# ds7_redraw.net
KiCad netlist of a schematic drawn in EAGLE
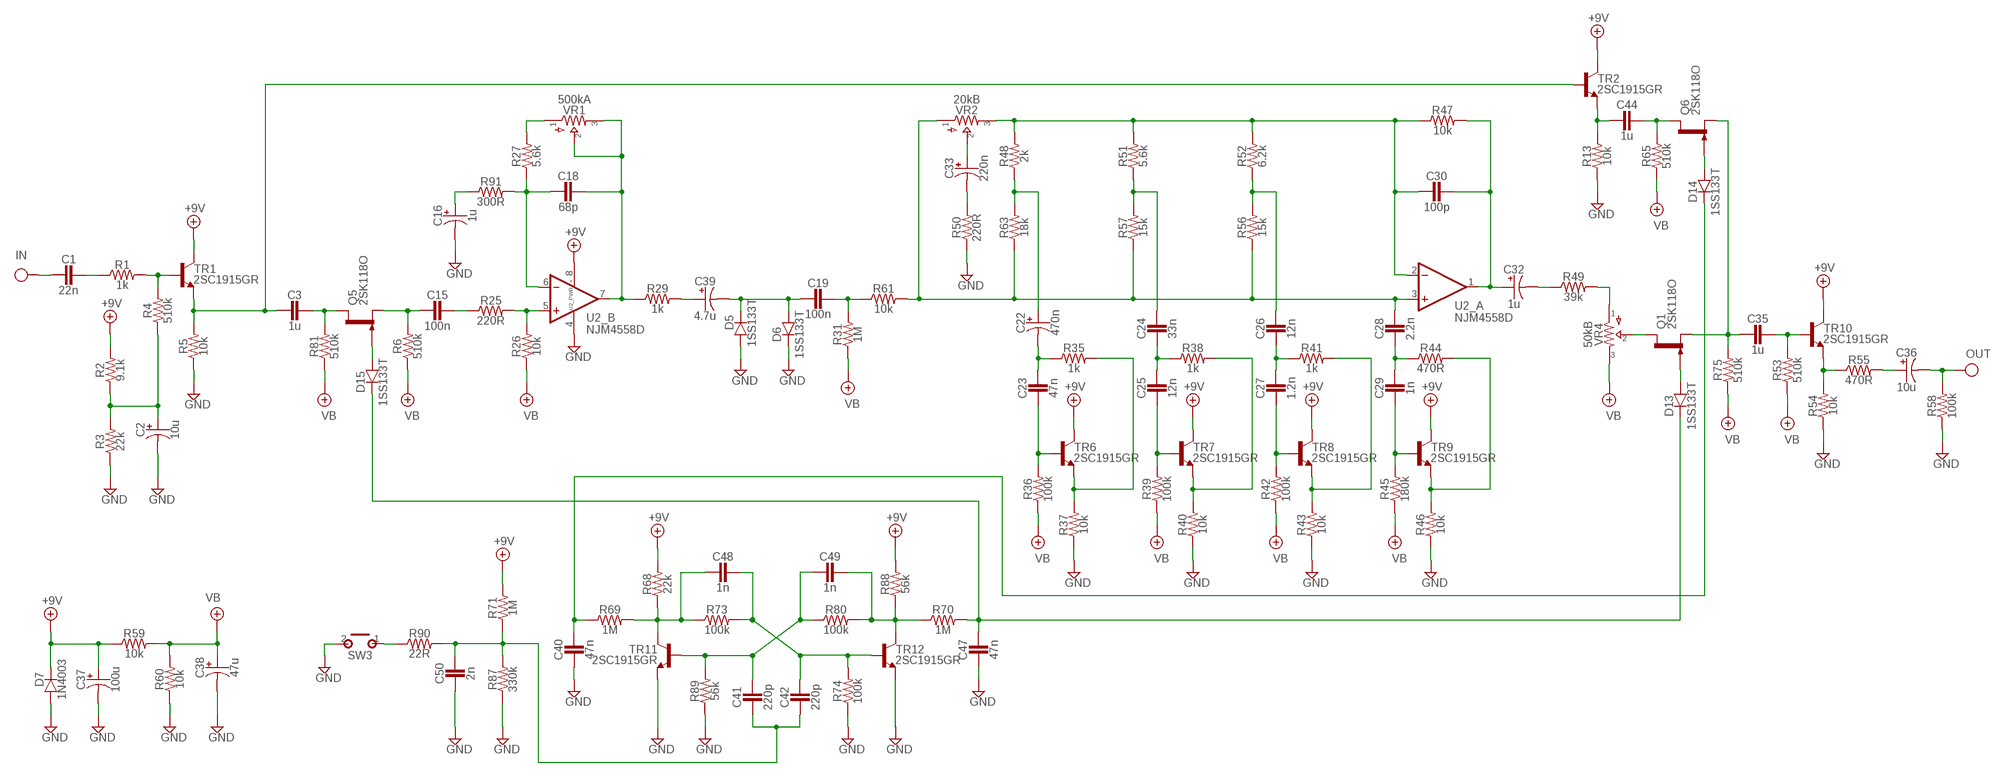
[diagram p0: schematic, sheet 1]

(export (version "E")
  (design (tool "Eeschema 10.0.6"))
  (components
    (comp (ref "C1")
      (value "22n")
      (footprint "eagle-import:BOX_SMALL")
      (libsource (lib "eagle-import") (part "CER/FILMBOX.1"))
    )
    (comp (ref "C2")
      (value "10u")
      (footprint "eagle-import:040_020")
      (libsource (lib "eagle-import") (part "0400"))
    )
    (comp (ref "C3")
      (value "1u")
      (footprint "eagle-import:BOX_SMALL")
      (libsource (lib "eagle-import") (part "CER/FILMBOX.1"))
    )
    (comp (ref "C15")
      (value "100n")
      (footprint "eagle-import:BOX_SMALL")
      (libsource (lib "eagle-import") (part "CER/FILMBOX.1"))
    )
    (comp (ref "C16")
      (value "1u")
      (footprint "eagle-import:040_020")
      (libsource (lib "eagle-import") (part "0400"))
    )
    (comp (ref "C18")
      (value "68p")
      (footprint "eagle-import:BOX_SMALL")
      (libsource (lib "eagle-import") (part "CER/FILMBOX.1"))
    )
    (comp (ref "C19")
      (value "100n")
      (footprint "eagle-import:BOX_SMALL")
      (libsource (lib "eagle-import") (part "CER/FILMBOX.1"))
    )
    (comp (ref "C22")
      (value "470n")
      (footprint "eagle-import:040_020")
      (libsource (lib "eagle-import") (part "0400"))
    )
    (comp (ref "C23")
      (value "47n")
      (footprint "eagle-import:BOX_SMALL")
      (libsource (lib "eagle-import") (part "CER/FILMBOX.1"))
    )
    (comp (ref "C24")
      (value "33n")
      (footprint "eagle-import:BOX_SMALL")
      (libsource (lib "eagle-import") (part "CER/FILMBOX.1"))
    )
    (comp (ref "C25")
      (value "12n")
      (footprint "eagle-import:BOX_SMALL")
      (libsource (lib "eagle-import") (part "CER/FILMBOX.1"))
    )
    (comp (ref "C26")
      (value "12n")
      (footprint "eagle-import:BOX_SMALL")
      (libsource (lib "eagle-import") (part "CER/FILMBOX.1"))
    )
    (comp (ref "C27")
      (value "1.2n")
      (footprint "eagle-import:BOX_SMALL")
      (libsource (lib "eagle-import") (part "CER/FILMBOX.1"))
    )
    (comp (ref "C28")
      (value "2.2n")
      (footprint "eagle-import:BOX_SMALL")
      (libsource (lib "eagle-import") (part "CER/FILMBOX.1"))
    )
    (comp (ref "C29")
      (value "1n")
      (footprint "eagle-import:BOX_SMALL")
      (libsource (lib "eagle-import") (part "CER/FILMBOX.1"))
    )
    (comp (ref "C30")
      (value "100p")
      (footprint "eagle-import:BOX_SMALL")
      (libsource (lib "eagle-import") (part "CER/FILMBOX.1"))
    )
    (comp (ref "C32")
      (value "1u")
      (footprint "eagle-import:040_020")
      (libsource (lib "eagle-import") (part "0400"))
    )
    (comp (ref "C33")
      (value "220n")
      (footprint "eagle-import:040_020")
      (libsource (lib "eagle-import") (part "0400"))
    )
    (comp (ref "C35")
      (value "1u")
      (footprint "eagle-import:BOX_SMALL")
      (libsource (lib "eagle-import") (part "CER/FILMBOX.1"))
    )
    (comp (ref "C36")
      (value "10u")
      (footprint "eagle-import:040_020")
      (libsource (lib "eagle-import") (part "0400"))
    )
    (comp (ref "C37")
      (value "100u")
      (footprint "eagle-import:040_020")
      (libsource (lib "eagle-import") (part "0400"))
    )
    (comp (ref "C38")
      (value "47u")
      (footprint "eagle-import:040_020")
      (libsource (lib "eagle-import") (part "0400"))
    )
    (comp (ref "C39")
      (value "4.7u")
      (footprint "eagle-import:040_020")
      (libsource (lib "eagle-import") (part "0400"))
    )
    (comp (ref "C40")
      (value "47n")
      (footprint "eagle-import:BOX_SMALL")
      (libsource (lib "eagle-import") (part "CER/FILMBOX.1"))
    )
    (comp (ref "C41")
      (value "220p")
      (footprint "eagle-import:BOX_SMALL")
      (libsource (lib "eagle-import") (part "CER/FILMBOX.1"))
    )
    (comp (ref "C42")
      (value "220p")
      (footprint "eagle-import:BOX_SMALL")
      (libsource (lib "eagle-import") (part "CER/FILMBOX.1"))
    )
    (comp (ref "C44")
      (value "1u")
      (footprint "eagle-import:BOX_SMALL")
      (libsource (lib "eagle-import") (part "CER/FILMBOX.1"))
    )
    (comp (ref "C47")
      (value "47n")
      (footprint "eagle-import:BOX_SMALL")
      (libsource (lib "eagle-import") (part "CER/FILMBOX.1"))
    )
    (comp (ref "C48")
      (value "1n")
      (footprint "eagle-import:BOX_SMALL")
      (libsource (lib "eagle-import") (part "CER/FILMBOX.1"))
    )
    (comp (ref "C49")
      (value "1n")
      (footprint "eagle-import:BOX_SMALL")
      (libsource (lib "eagle-import") (part "CER/FILMBOX.1"))
    )
    (comp (ref "C50")
      (value "2n")
      (footprint "eagle-import:BOX_SMALL")
      (libsource (lib "eagle-import") (part "CER/FILMBOX.1"))
    )
    (comp (ref "D5")
      (value "1SS133T")
      (footprint "eagle-import:DO41-2")
      (libsource (lib "eagle-import") (part "DO41.2"))
    )
    (comp (ref "D6")
      (value "1SS133T")
      (footprint "eagle-import:DO41-2")
      (libsource (lib "eagle-import") (part "DO41.2"))
    )
    (comp (ref "D7")
      (value "1N4003")
      (footprint "eagle-import:DO41-2")
      (libsource (lib "eagle-import") (part "DO41.2"))
    )
    (comp (ref "D13")
      (value "1SS133T")
      (footprint "eagle-import:DO41-2")
      (libsource (lib "eagle-import") (part "DO41.2"))
    )
    (comp (ref "D14")
      (value "1SS133T")
      (footprint "eagle-import:DO41-2")
      (libsource (lib "eagle-import") (part "DO41.2"))
    )
    (comp (ref "D15")
      (value "1SS133T")
      (footprint "eagle-import:DO41-2")
      (libsource (lib "eagle-import") (part "DO41.2"))
    )
    (comp (ref "Q1")
      (value "2SK118O")
      (footprint "eagle-import:TO92-")
      (libsource (lib "eagle-import") (part "2N5457"))
    )
    (comp (ref "Q5")
      (value "2SK118O")
      (footprint "eagle-import:TO92-")
      (libsource (lib "eagle-import") (part "2N5457"))
    )
    (comp (ref "Q6")
      (value "2SK118O")
      (footprint "eagle-import:TO92-")
      (libsource (lib "eagle-import") (part "2N5457"))
    )
    (comp (ref "R1")
      (value "1k")
      (footprint "eagle-import:R0207_3")
      (libsource (lib "eagle-import") (part "R_.3B"))
    )
    (comp (ref "R2")
      (value "9.1k")
      (footprint "eagle-import:R0207_3")
      (libsource (lib "eagle-import") (part "R_.3B"))
    )
    (comp (ref "R3")
      (value "22k")
      (footprint "eagle-import:R0207_3")
      (libsource (lib "eagle-import") (part "R_.3B"))
    )
    (comp (ref "R4")
      (value "510k")
      (footprint "eagle-import:R0207_3")
      (libsource (lib "eagle-import") (part "R_.3B"))
    )
    (comp (ref "R5")
      (value "10k")
      (footprint "eagle-import:R0207_3")
      (libsource (lib "eagle-import") (part "R_.3B"))
    )
    (comp (ref "R6")
      (value "510k")
      (footprint "eagle-import:R0207_3")
      (libsource (lib "eagle-import") (part "R_.3B"))
    )
    (comp (ref "R13")
      (value "10k")
      (footprint "eagle-import:R0207_3")
      (libsource (lib "eagle-import") (part "R_.3B"))
    )
    (comp (ref "R25")
      (value "220R")
      (footprint "eagle-import:R0207_3")
      (libsource (lib "eagle-import") (part "R_.3B"))
    )
    (comp (ref "R26")
      (value "10k")
      (footprint "eagle-import:R0207_3")
      (libsource (lib "eagle-import") (part "R_.3B"))
    )
    (comp (ref "R27")
      (value "5.6k")
      (footprint "eagle-import:R0207_3")
      (libsource (lib "eagle-import") (part "R_.3B"))
    )
    (comp (ref "R29")
      (value "1k")
      (footprint "eagle-import:R0207_3")
      (libsource (lib "eagle-import") (part "R_.3B"))
    )
    (comp (ref "R31")
      (value "1M")
      (footprint "eagle-import:R0207_3")
      (libsource (lib "eagle-import") (part "R_.3B"))
    )
    (comp (ref "R35")
      (value "1k")
      (footprint "eagle-import:R0207_3")
      (libsource (lib "eagle-import") (part "R_.3B"))
    )
    (comp (ref "R36")
      (value "100k")
      (footprint "eagle-import:R0207_3")
      (libsource (lib "eagle-import") (part "R_.3B"))
    )
    (comp (ref "R37")
      (value "10k")
      (footprint "eagle-import:R0207_3")
      (libsource (lib "eagle-import") (part "R_.3B"))
    )
    (comp (ref "R38")
      (value "1k")
      (footprint "eagle-import:R0207_3")
      (libsource (lib "eagle-import") (part "R_.3B"))
    )
    (comp (ref "R39")
      (value "100k")
      (footprint "eagle-import:R0207_3")
      (libsource (lib "eagle-import") (part "R_.3B"))
    )
    (comp (ref "R40")
      (value "10k")
      (footprint "eagle-import:R0207_3")
      (libsource (lib "eagle-import") (part "R_.3B"))
    )
    (comp (ref "R41")
      (value "1k")
      (footprint "eagle-import:R0207_3")
      (libsource (lib "eagle-import") (part "R_.3B"))
    )
    (comp (ref "R42")
      (value "100k")
      (footprint "eagle-import:R0207_3")
      (libsource (lib "eagle-import") (part "R_.3B"))
    )
    (comp (ref "R43")
      (value "10k")
      (footprint "eagle-import:R0207_3")
      (libsource (lib "eagle-import") (part "R_.3B"))
    )
    (comp (ref "R44")
      (value "470R")
      (footprint "eagle-import:R0207_3")
      (libsource (lib "eagle-import") (part "R_.3B"))
    )
    (comp (ref "R45")
      (value "180k")
      (footprint "eagle-import:R0207_3")
      (libsource (lib "eagle-import") (part "R_.3B"))
    )
    (comp (ref "R46")
      (value "10k")
      (footprint "eagle-import:R0207_3")
      (libsource (lib "eagle-import") (part "R_.3B"))
    )
    (comp (ref "R47")
      (value "10k")
      (footprint "eagle-import:R0207_3")
      (libsource (lib "eagle-import") (part "R_.3B"))
    )
    (comp (ref "R48")
      (value "2k")
      (footprint "eagle-import:R0207_3")
      (libsource (lib "eagle-import") (part "R_.3B"))
    )
    (comp (ref "R49")
      (value "39k")
      (footprint "eagle-import:R0207_3")
      (libsource (lib "eagle-import") (part "R_.3B"))
    )
    (comp (ref "R50")
      (value "220R")
      (footprint "eagle-import:R0207_3")
      (libsource (lib "eagle-import") (part "R_.3B"))
    )
    (comp (ref "R51")
      (value "5.6k")
      (footprint "eagle-import:R0207_3")
      (libsource (lib "eagle-import") (part "R_.3B"))
    )
    (comp (ref "R52")
      (value "6.2k")
      (footprint "eagle-import:R0207_3")
      (libsource (lib "eagle-import") (part "R_.3B"))
    )
    (comp (ref "R53")
      (value "510k")
      (footprint "eagle-import:R0207_3")
      (libsource (lib "eagle-import") (part "R_.3B"))
    )
    (comp (ref "R54")
      (value "10k")
      (footprint "eagle-import:R0207_3")
      (libsource (lib "eagle-import") (part "R_.3B"))
    )
    (comp (ref "R55")
      (value "470R")
      (footprint "eagle-import:R0207_3")
      (libsource (lib "eagle-import") (part "R_.3B"))
    )
    (comp (ref "R56")
      (value "15k")
      (footprint "eagle-import:R0207_3")
      (libsource (lib "eagle-import") (part "R_.3B"))
    )
    (comp (ref "R57")
      (value "15k")
      (footprint "eagle-import:R0207_3")
      (libsource (lib "eagle-import") (part "R_.3B"))
    )
    (comp (ref "R58")
      (value "100k")
      (footprint "eagle-import:R0207_3")
      (libsource (lib "eagle-import") (part "R_.3B"))
    )
    (comp (ref "R59")
      (value "10k")
      (footprint "eagle-import:R0207_3")
      (libsource (lib "eagle-import") (part "R_.3B"))
    )
    (comp (ref "R60")
      (value "10k")
      (footprint "eagle-import:R0207_3")
      (libsource (lib "eagle-import") (part "R_.3B"))
    )
    (comp (ref "R61")
      (value "10k")
      (footprint "eagle-import:R0207_3")
      (libsource (lib "eagle-import") (part "R_.3B"))
    )
    (comp (ref "R63")
      (value "18k")
      (footprint "eagle-import:R0207_3")
      (libsource (lib "eagle-import") (part "R_.3B"))
    )
    (comp (ref "R65")
      (value "510k")
      (footprint "eagle-import:R0207_3")
      (libsource (lib "eagle-import") (part "R_.3B"))
    )
    (comp (ref "R68")
      (value "22k")
      (footprint "eagle-import:R0207_3")
      (libsource (lib "eagle-import") (part "R_.3B"))
    )
    (comp (ref "R69")
      (value "1M")
      (footprint "eagle-import:R0207_3")
      (libsource (lib "eagle-import") (part "R_.3B"))
    )
    (comp (ref "R70")
      (value "1M")
      (footprint "eagle-import:R0207_3")
      (libsource (lib "eagle-import") (part "R_.3B"))
    )
    (comp (ref "R71")
      (value "1M")
      (footprint "eagle-import:R0207_3")
      (libsource (lib "eagle-import") (part "R_.3B"))
    )
    (comp (ref "R73")
      (value "100k")
      (footprint "eagle-import:R0207_3")
      (libsource (lib "eagle-import") (part "R_.3B"))
    )
    (comp (ref "R74")
      (value "100k")
      (footprint "eagle-import:R0207_3")
      (libsource (lib "eagle-import") (part "R_.3B"))
    )
    (comp (ref "R75")
      (value "510k")
      (footprint "eagle-import:R0207_3")
      (libsource (lib "eagle-import") (part "R_.3B"))
    )
    (comp (ref "R80")
      (value "100k")
      (footprint "eagle-import:R0207_3")
      (libsource (lib "eagle-import") (part "R_.3B"))
    )
    (comp (ref "R81")
      (value "510k")
      (footprint "eagle-import:R0207_3")
      (libsource (lib "eagle-import") (part "R_.3B"))
    )
    (comp (ref "R87")
      (value "330k")
      (footprint "eagle-import:R0207_3")
      (libsource (lib "eagle-import") (part "R_.3B"))
    )
    (comp (ref "R88")
      (value "56k")
      (footprint "eagle-import:R0207_3")
      (libsource (lib "eagle-import") (part "R_.3B"))
    )
    (comp (ref "R89")
      (value "56k")
      (footprint "eagle-import:R0207_3")
      (libsource (lib "eagle-import") (part "R_.3B"))
    )
    (comp (ref "R90")
      (value "22R")
      (footprint "eagle-import:R0207_3")
      (libsource (lib "eagle-import") (part "R_.3B"))
    )
    (comp (ref "R91")
      (value "300R")
      (footprint "eagle-import:R0207_3")
      (libsource (lib "eagle-import") (part "R_.3B"))
    )
    (comp (ref "SW3")
      (value "MOMENTARY")
      (footprint "eagle-import:SPST")
      (libsource (lib "eagle-import") (part "MOMENTARY"))
    )
    (comp (ref "TR1")
      (value "2SC1915GR")
      (footprint "eagle-import:TO92-")
      (libsource (lib "eagle-import") (part "2SC828A"))
    )
    (comp (ref "TR2")
      (value "2SC1915GR")
      (footprint "eagle-import:TO92-")
      (libsource (lib "eagle-import") (part "2SC828A"))
    )
    (comp (ref "TR6")
      (value "2SC1915GR")
      (footprint "eagle-import:TO92-")
      (libsource (lib "eagle-import") (part "2SC828A"))
    )
    (comp (ref "TR7")
      (value "2SC1915GR")
      (footprint "eagle-import:TO92-")
      (libsource (lib "eagle-import") (part "2SC828A"))
    )
    (comp (ref "TR8")
      (value "2SC1915GR")
      (footprint "eagle-import:TO92-")
      (libsource (lib "eagle-import") (part "2SC828A"))
    )
    (comp (ref "TR9")
      (value "2SC1915GR")
      (footprint "eagle-import:TO92-")
      (libsource (lib "eagle-import") (part "2SC828A"))
    )
    (comp (ref "TR10")
      (value "2SC1915GR")
      (footprint "eagle-import:TO92-")
      (libsource (lib "eagle-import") (part "2SC828A"))
    )
    (comp (ref "TR11")
      (value "2SC1915GR")
      (footprint "eagle-import:TO92-")
      (libsource (lib "eagle-import") (part "2SC828A"))
    )
    (comp (ref "TR12")
      (value "2SC1915GR")
      (footprint "eagle-import:TO92-")
      (libsource (lib "eagle-import") (part "2SC828A"))
    )
    (comp (ref "U2")
      (value "NJM4558D")
      (footprint "eagle-import:DIL0")
      (libsource (lib "eagle-import") (part "DUALTH"))
    )
    (comp (ref "VR1")
      (value "500kA")
      (footprint "eagle-import:16MM")
      (libsource (lib "eagle-import") (part "POTS16MM"))
    )
    (comp (ref "VR2")
      (value "20kB")
      (footprint "eagle-import:16MM")
      (libsource (lib "eagle-import") (part "POTS16MM"))
    )
    (comp (ref "VR4")
      (value "50kB")
      (footprint "eagle-import:16MM")
      (libsource (lib "eagle-import") (part "POTS16MM"))
    )
  )
  (nets
    (net (code "1") (name "+9V") (class "Default")
      (node (ref "C37") (pin "+") (pinfunction "+_+") (pintype "passive"))
      (node (ref "D7") (pin "C") (pinfunction "C_C") (pintype "passive"))
      (node (ref "R2") (pin "2") (pinfunction "2_2") (pintype "passive"))
      (node (ref "R59") (pin "1") (pinfunction "1_1") (pintype "passive"))
      (node (ref "R68") (pin "2") (pinfunction "2_2") (pintype "passive"))
      (node (ref "R71") (pin "2") (pinfunction "2_2") (pintype "passive"))
      (node (ref "R88") (pin "2") (pinfunction "2_2") (pintype "passive"))
      (node (ref "TR1") (pin "2") (pinfunction "C_2") (pintype "passive"))
      (node (ref "TR10") (pin "2") (pinfunction "C_2") (pintype "passive"))
      (node (ref "TR2") (pin "2") (pinfunction "C_2") (pintype "passive"))
      (node (ref "TR6") (pin "2") (pinfunction "C_2") (pintype "passive"))
      (node (ref "TR7") (pin "2") (pinfunction "C_2") (pintype "passive"))
      (node (ref "TR8") (pin "2") (pinfunction "C_2") (pintype "passive"))
      (node (ref "TR9") (pin "2") (pinfunction "C_2") (pintype "passive"))
      (node (ref "U2") (pin "8") (pinfunction "V+_8") (pintype "power_in"))
    )
    (net (code "2") (name "GND") (class "Default")
      (node (ref "C16") (pin "-") (pinfunction "-_-") (pintype "passive"))
      (node (ref "C2") (pin "-") (pinfunction "-_-") (pintype "passive"))
      (node (ref "C37") (pin "-") (pinfunction "-_-") (pintype "passive"))
      (node (ref "C38") (pin "-") (pinfunction "-_-") (pintype "passive"))
      (node (ref "C40") (pin "2") (pinfunction "2_2") (pintype "passive"))
      (node (ref "C47") (pin "2") (pinfunction "2_2") (pintype "passive"))
      (node (ref "C50") (pin "2") (pinfunction "2_2") (pintype "passive"))
      (node (ref "D5") (pin "A") (pinfunction "A_A") (pintype "passive"))
      (node (ref "D6") (pin "C") (pinfunction "C_C") (pintype "passive"))
      (node (ref "D7") (pin "A") (pinfunction "A_A") (pintype "passive"))
      (node (ref "R13") (pin "1") (pinfunction "1_1") (pintype "passive"))
      (node (ref "R3") (pin "1") (pinfunction "1_1") (pintype "passive"))
      (node (ref "R37") (pin "1") (pinfunction "1_1") (pintype "passive"))
      (node (ref "R40") (pin "1") (pinfunction "1_1") (pintype "passive"))
      (node (ref "R43") (pin "1") (pinfunction "1_1") (pintype "passive"))
      (node (ref "R46") (pin "1") (pinfunction "1_1") (pintype "passive"))
      (node (ref "R5") (pin "1") (pinfunction "1_1") (pintype "passive"))
      (node (ref "R50") (pin "1") (pinfunction "1_1") (pintype "passive"))
      (node (ref "R54") (pin "1") (pinfunction "1_1") (pintype "passive"))
      (node (ref "R58") (pin "1") (pinfunction "1_1") (pintype "passive"))
      (node (ref "R60") (pin "1") (pinfunction "1_1") (pintype "passive"))
      (node (ref "R74") (pin "1") (pinfunction "1_1") (pintype "passive"))
      (node (ref "R87") (pin "1") (pinfunction "1_1") (pintype "passive"))
      (node (ref "R89") (pin "1") (pinfunction "1_1") (pintype "passive"))
      (node (ref "SW3") (pin "2") (pinfunction "S_2") (pintype "passive"))
      (node (ref "TR11") (pin "3") (pinfunction "E_3") (pintype "passive"))
      (node (ref "TR12") (pin "3") (pinfunction "E_3") (pintype "passive"))
      (node (ref "U2") (pin "4") (pinfunction "V-_4") (pintype "power_in"))
    )
    (net (code "3") (name "IN") (class "Default")
      (node (ref "C1") (pin "2") (pinfunction "2_2") (pintype "passive"))
    )
    (net (code "4") (name "Net-(C1-Pad1)") (class "Default")
      (node (ref "C1") (pin "1") (pinfunction "1_1") (pintype "passive"))
      (node (ref "R1") (pin "1") (pinfunction "1_1") (pintype "passive"))
    )
    (net (code "5") (name "Net-(C2-Pad+)") (class "Default")
      (node (ref "C2") (pin "+") (pinfunction "+_+") (pintype "passive"))
      (node (ref "R2") (pin "1") (pinfunction "1_1") (pintype "passive"))
      (node (ref "R3") (pin "2") (pinfunction "2_2") (pintype "passive"))
      (node (ref "R4") (pin "1") (pinfunction "1_1") (pintype "passive"))
    )
    (net (code "6") (name "Net-(C15-Pad1)") (class "Default")
      (node (ref "C15") (pin "1") (pinfunction "1_1") (pintype "passive"))
      (node (ref "R25") (pin "1") (pinfunction "1_1") (pintype "passive"))
    )
    (net (code "7") (name "Net-(C16-Pad+)") (class "Default")
      (node (ref "C16") (pin "+") (pinfunction "+_+") (pintype "passive"))
      (node (ref "R91") (pin "1") (pinfunction "1_1") (pintype "passive"))
    )
    (net (code "8") (name "Net-(C19-Pad1)") (class "Default")
      (node (ref "C19") (pin "1") (pinfunction "1_1") (pintype "passive"))
      (node (ref "R31") (pin "2") (pinfunction "2_2") (pintype "passive"))
      (node (ref "R61") (pin "1") (pinfunction "1_1") (pintype "passive"))
    )
    (net (code "9") (name "Net-(C19-Pad2)") (class "Default")
      (node (ref "C19") (pin "2") (pinfunction "2_2") (pintype "passive"))
      (node (ref "C39") (pin "-") (pinfunction "-_-") (pintype "passive"))
      (node (ref "D5") (pin "C") (pinfunction "C_C") (pintype "passive"))
      (node (ref "D6") (pin "A") (pinfunction "A_A") (pintype "passive"))
    )
    (net (code "10") (name "Net-(C22-Pad+)") (class "Default")
      (node (ref "C22") (pin "+") (pinfunction "+_+") (pintype "passive"))
      (node (ref "R48") (pin "1") (pinfunction "1_1") (pintype "passive"))
      (node (ref "R63") (pin "2") (pinfunction "2_2") (pintype "passive"))
    )
    (net (code "11") (name "Net-(C22-Pad-)") (class "Default")
      (node (ref "C22") (pin "-") (pinfunction "-_-") (pintype "passive"))
      (node (ref "C23") (pin "1") (pinfunction "1_1") (pintype "passive"))
      (node (ref "R35") (pin "1") (pinfunction "1_1") (pintype "passive"))
    )
    (net (code "12") (name "Net-(C24-Pad1)") (class "Default")
      (node (ref "C24") (pin "1") (pinfunction "1_1") (pintype "passive"))
      (node (ref "R51") (pin "1") (pinfunction "1_1") (pintype "passive"))
      (node (ref "R57") (pin "2") (pinfunction "2_2") (pintype "passive"))
    )
    (net (code "13") (name "Net-(C24-Pad2)") (class "Default")
      (node (ref "C24") (pin "2") (pinfunction "2_2") (pintype "passive"))
      (node (ref "C25") (pin "1") (pinfunction "1_1") (pintype "passive"))
      (node (ref "R38") (pin "1") (pinfunction "1_1") (pintype "passive"))
    )
    (net (code "14") (name "Net-(C26-Pad1)") (class "Default")
      (node (ref "C26") (pin "1") (pinfunction "1_1") (pintype "passive"))
      (node (ref "R52") (pin "1") (pinfunction "1_1") (pintype "passive"))
      (node (ref "R56") (pin "2") (pinfunction "2_2") (pintype "passive"))
    )
    (net (code "15") (name "Net-(C26-Pad2)") (class "Default")
      (node (ref "C26") (pin "2") (pinfunction "2_2") (pintype "passive"))
      (node (ref "C27") (pin "1") (pinfunction "1_1") (pintype "passive"))
      (node (ref "R41") (pin "1") (pinfunction "1_1") (pintype "passive"))
    )
    (net (code "16") (name "Net-(C28-Pad2)") (class "Default")
      (node (ref "C28") (pin "2") (pinfunction "2_2") (pintype "passive"))
      (node (ref "C29") (pin "1") (pinfunction "1_1") (pintype "passive"))
      (node (ref "R44") (pin "1") (pinfunction "1_1") (pintype "passive"))
    )
    (net (code "17") (name "Net-(C32-Pad-)") (class "Default")
      (node (ref "C32") (pin "-") (pinfunction "-_-") (pintype "passive"))
      (node (ref "R49") (pin "1") (pinfunction "1_1") (pintype "passive"))
    )
    (net (code "18") (name "Net-(C33-Pad+)") (class "Default")
      (node (ref "C33") (pin "+") (pinfunction "+_+") (pintype "passive"))
      (node (ref "VR2") (pin "2") (pinfunction "2_2") (pintype "passive"))
    )
    (net (code "19") (name "Net-(C33-Pad-)") (class "Default")
      (node (ref "C33") (pin "-") (pinfunction "-_-") (pintype "passive"))
      (node (ref "R50") (pin "2") (pinfunction "2_2") (pintype "passive"))
    )
    (net (code "20") (name "Net-(C36-Pad+)") (class "Default")
      (node (ref "C36") (pin "+") (pinfunction "+_+") (pintype "passive"))
      (node (ref "R55") (pin "2") (pinfunction "2_2") (pintype "passive"))
    )
    (net (code "21") (name "Net-(C39-Pad+)") (class "Default")
      (node (ref "C39") (pin "+") (pinfunction "+_+") (pintype "passive"))
      (node (ref "R29") (pin "2") (pinfunction "2_2") (pintype "passive"))
    )
    (net (code "22") (name "Net-(C40-Pad1)") (class "Default")
      (node (ref "C40") (pin "1") (pinfunction "1_1") (pintype "passive"))
      (node (ref "D14") (pin "C") (pinfunction "C_C") (pintype "passive"))
      (node (ref "R69") (pin "1") (pinfunction "1_1") (pintype "passive"))
    )
    (net (code "23") (name "Net-(C41-Pad2)") (class "Default")
      (node (ref "C41") (pin "2") (pinfunction "2_2") (pintype "passive"))
      (node (ref "C42") (pin "2") (pinfunction "2_2") (pintype "passive"))
      (node (ref "C50") (pin "1") (pinfunction "1_1") (pintype "passive"))
      (node (ref "R71") (pin "1") (pinfunction "1_1") (pintype "passive"))
      (node (ref "R87") (pin "2") (pinfunction "2_2") (pintype "passive"))
      (node (ref "R90") (pin "2") (pinfunction "2_2") (pintype "passive"))
    )
    (net (code "24") (name "Net-(C47-Pad1)") (class "Default")
      (node (ref "C47") (pin "1") (pinfunction "1_1") (pintype "passive"))
      (node (ref "D13") (pin "C") (pinfunction "C_C") (pintype "passive"))
      (node (ref "D15") (pin "C") (pinfunction "C_C") (pintype "passive"))
      (node (ref "R70") (pin "2") (pinfunction "2_2") (pintype "passive"))
    )
    (net (code "25") (name "Net-(Q1-D)") (class "Default")
      (node (ref "Q1") (pin "3") (pinfunction "D_3") (pintype "passive"))
      (node (ref "VR4") (pin "2") (pinfunction "2_2") (pintype "passive"))
    )
    (net (code "26") (name "Net-(Q1-G)") (class "Default")
      (node (ref "D13") (pin "A") (pinfunction "A_A") (pintype "passive"))
      (node (ref "Q1") (pin "1") (pinfunction "G_1") (pintype "passive"))
    )
    (net (code "27") (name "Net-(Q1-S)") (class "Default")
      (node (ref "C35") (pin "2") (pinfunction "2_2") (pintype "passive"))
      (node (ref "Q1") (pin "2") (pinfunction "S_2") (pintype "passive"))
      (node (ref "Q6") (pin "2") (pinfunction "S_2") (pintype "passive"))
      (node (ref "R75") (pin "2") (pinfunction "2_2") (pintype "passive"))
    )
    (net (code "28") (name "Net-(Q5-D)") (class "Default")
      (node (ref "C3") (pin "1") (pinfunction "1_1") (pintype "passive"))
      (node (ref "Q5") (pin "3") (pinfunction "D_3") (pintype "passive"))
      (node (ref "R81") (pin "2") (pinfunction "2_2") (pintype "passive"))
    )
    (net (code "29") (name "Net-(Q5-G)") (class "Default")
      (node (ref "D15") (pin "A") (pinfunction "A_A") (pintype "passive"))
      (node (ref "Q5") (pin "1") (pinfunction "G_1") (pintype "passive"))
    )
    (net (code "30") (name "Net-(Q5-S)") (class "Default")
      (node (ref "C15") (pin "2") (pinfunction "2_2") (pintype "passive"))
      (node (ref "Q5") (pin "2") (pinfunction "S_2") (pintype "passive"))
      (node (ref "R6") (pin "2") (pinfunction "2_2") (pintype "passive"))
    )
    (net (code "31") (name "Net-(Q6-D)") (class "Default")
      (node (ref "C44") (pin "1") (pinfunction "1_1") (pintype "passive"))
      (node (ref "Q6") (pin "3") (pinfunction "D_3") (pintype "passive"))
      (node (ref "R65") (pin "2") (pinfunction "2_2") (pintype "passive"))
    )
    (net (code "32") (name "Net-(Q6-G)") (class "Default")
      (node (ref "D14") (pin "A") (pinfunction "A_A") (pintype "passive"))
      (node (ref "Q6") (pin "1") (pinfunction "G_1") (pintype "passive"))
    )
    (net (code "33") (name "Net-(R27-Pad2)") (class "Default")
      (node (ref "R27") (pin "2") (pinfunction "2_2") (pintype "passive"))
      (node (ref "VR1") (pin "1") (pinfunction "1_1") (pintype "passive"))
    )
    (net (code "34") (name "Net-(R49-Pad2)") (class "Default")
      (node (ref "R49") (pin "2") (pinfunction "2_2") (pintype "passive"))
      (node (ref "VR4") (pin "1") (pinfunction "1_1") (pintype "passive"))
    )
    (net (code "35") (name "Net-(SW3-P)") (class "Default")
      (node (ref "R90") (pin "1") (pinfunction "1_1") (pintype "passive"))
      (node (ref "SW3") (pin "1") (pinfunction "P_1") (pintype "passive"))
    )
    (net (code "36") (name "Net-(TR1-B)") (class "Default")
      (node (ref "R1") (pin "2") (pinfunction "2_2") (pintype "passive"))
      (node (ref "R4") (pin "2") (pinfunction "2_2") (pintype "passive"))
      (node (ref "TR1") (pin "1") (pinfunction "B_1") (pintype "passive"))
    )
    (net (code "37") (name "Net-(TR1-E)") (class "Default")
      (node (ref "C3") (pin "2") (pinfunction "2_2") (pintype "passive"))
      (node (ref "R5") (pin "2") (pinfunction "2_2") (pintype "passive"))
      (node (ref "TR1") (pin "3") (pinfunction "E_3") (pintype "passive"))
      (node (ref "TR2") (pin "1") (pinfunction "B_1") (pintype "passive"))
    )
    (net (code "38") (name "Net-(TR2-E)") (class "Default")
      (node (ref "C44") (pin "2") (pinfunction "2_2") (pintype "passive"))
      (node (ref "R13") (pin "2") (pinfunction "2_2") (pintype "passive"))
      (node (ref "TR2") (pin "3") (pinfunction "E_3") (pintype "passive"))
    )
    (net (code "39") (name "Net-(TR6-B)") (class "Default")
      (node (ref "C23") (pin "2") (pinfunction "2_2") (pintype "passive"))
      (node (ref "R36") (pin "2") (pinfunction "2_2") (pintype "passive"))
      (node (ref "TR6") (pin "1") (pinfunction "B_1") (pintype "passive"))
    )
    (net (code "40") (name "Net-(TR6-E)") (class "Default")
      (node (ref "R35") (pin "2") (pinfunction "2_2") (pintype "passive"))
      (node (ref "R37") (pin "2") (pinfunction "2_2") (pintype "passive"))
      (node (ref "TR6") (pin "3") (pinfunction "E_3") (pintype "passive"))
    )
    (net (code "41") (name "Net-(TR7-B)") (class "Default")
      (node (ref "C25") (pin "2") (pinfunction "2_2") (pintype "passive"))
      (node (ref "R39") (pin "2") (pinfunction "2_2") (pintype "passive"))
      (node (ref "TR7") (pin "1") (pinfunction "B_1") (pintype "passive"))
    )
    (net (code "42") (name "Net-(TR7-E)") (class "Default")
      (node (ref "R38") (pin "2") (pinfunction "2_2") (pintype "passive"))
      (node (ref "R40") (pin "2") (pinfunction "2_2") (pintype "passive"))
      (node (ref "TR7") (pin "3") (pinfunction "E_3") (pintype "passive"))
    )
    (net (code "43") (name "Net-(TR8-B)") (class "Default")
      (node (ref "C27") (pin "2") (pinfunction "2_2") (pintype "passive"))
      (node (ref "R42") (pin "2") (pinfunction "2_2") (pintype "passive"))
      (node (ref "TR8") (pin "1") (pinfunction "B_1") (pintype "passive"))
    )
    (net (code "44") (name "Net-(TR8-E)") (class "Default")
      (node (ref "R41") (pin "2") (pinfunction "2_2") (pintype "passive"))
      (node (ref "R43") (pin "2") (pinfunction "2_2") (pintype "passive"))
      (node (ref "TR8") (pin "3") (pinfunction "E_3") (pintype "passive"))
    )
    (net (code "45") (name "Net-(TR9-B)") (class "Default")
      (node (ref "C29") (pin "2") (pinfunction "2_2") (pintype "passive"))
      (node (ref "R45") (pin "2") (pinfunction "2_2") (pintype "passive"))
      (node (ref "TR9") (pin "1") (pinfunction "B_1") (pintype "passive"))
    )
    (net (code "46") (name "Net-(TR9-E)") (class "Default")
      (node (ref "R44") (pin "2") (pinfunction "2_2") (pintype "passive"))
      (node (ref "R46") (pin "2") (pinfunction "2_2") (pintype "passive"))
      (node (ref "TR9") (pin "3") (pinfunction "E_3") (pintype "passive"))
    )
    (net (code "47") (name "Net-(TR10-B)") (class "Default")
      (node (ref "C35") (pin "1") (pinfunction "1_1") (pintype "passive"))
      (node (ref "R53") (pin "2") (pinfunction "2_2") (pintype "passive"))
      (node (ref "TR10") (pin "1") (pinfunction "B_1") (pintype "passive"))
    )
    (net (code "48") (name "Net-(TR10-E)") (class "Default")
      (node (ref "R54") (pin "2") (pinfunction "2_2") (pintype "passive"))
      (node (ref "R55") (pin "1") (pinfunction "1_1") (pintype "passive"))
      (node (ref "TR10") (pin "3") (pinfunction "E_3") (pintype "passive"))
    )
    (net (code "49") (name "Net-(TR11-B)") (class "Default")
      (node (ref "C41") (pin "1") (pinfunction "1_1") (pintype "passive"))
      (node (ref "C49") (pin "2") (pinfunction "2_2") (pintype "passive"))
      (node (ref "R80") (pin "1") (pinfunction "1_1") (pintype "passive"))
      (node (ref "R89") (pin "2") (pinfunction "2_2") (pintype "passive"))
      (node (ref "TR11") (pin "1") (pinfunction "B_1") (pintype "passive"))
    )
    (net (code "50") (name "Net-(TR11-C)") (class "Default")
      (node (ref "C48") (pin "2") (pinfunction "2_2") (pintype "passive"))
      (node (ref "R68") (pin "1") (pinfunction "1_1") (pintype "passive"))
      (node (ref "R69") (pin "2") (pinfunction "2_2") (pintype "passive"))
      (node (ref "R73") (pin "1") (pinfunction "1_1") (pintype "passive"))
      (node (ref "TR11") (pin "2") (pinfunction "C_2") (pintype "passive"))
    )
    (net (code "51") (name "Net-(TR12-B)") (class "Default")
      (node (ref "C42") (pin "1") (pinfunction "1_1") (pintype "passive"))
      (node (ref "C48") (pin "1") (pinfunction "1_1") (pintype "passive"))
      (node (ref "R73") (pin "2") (pinfunction "2_2") (pintype "passive"))
      (node (ref "R74") (pin "2") (pinfunction "2_2") (pintype "passive"))
      (node (ref "TR12") (pin "1") (pinfunction "B_1") (pintype "passive"))
    )
    (net (code "52") (name "Net-(TR12-C)") (class "Default")
      (node (ref "C49") (pin "1") (pinfunction "1_1") (pintype "passive"))
      (node (ref "R70") (pin "1") (pinfunction "1_1") (pintype "passive"))
      (node (ref "R80") (pin "2") (pinfunction "2_2") (pintype "passive"))
      (node (ref "R88") (pin "1") (pinfunction "1_1") (pintype "passive"))
      (node (ref "TR12") (pin "2") (pinfunction "C_2") (pintype "passive"))
    )
    (net (code "53") (name "Net-(U2A-+IN)") (class "Default")
      (node (ref "C28") (pin "1") (pinfunction "1_1") (pintype "passive"))
      (node (ref "R56") (pin "1") (pinfunction "1_1") (pintype "passive"))
      (node (ref "R57") (pin "1") (pinfunction "1_1") (pintype "passive"))
      (node (ref "R61") (pin "2") (pinfunction "2_2") (pintype "passive"))
      (node (ref "R63") (pin "1") (pinfunction "1_1") (pintype "passive"))
      (node (ref "U2") (pin "3") (pinfunction "+IN_3") (pintype "input"))
      (node (ref "VR2") (pin "1") (pinfunction "1_1") (pintype "passive"))
    )
    (net (code "54") (name "Net-(U2A--IN)") (class "Default")
      (node (ref "C30") (pin "2") (pinfunction "2_2") (pintype "passive"))
      (node (ref "R47") (pin "1") (pinfunction "1_1") (pintype "passive"))
      (node (ref "R48") (pin "2") (pinfunction "2_2") (pintype "passive"))
      (node (ref "R51") (pin "2") (pinfunction "2_2") (pintype "passive"))
      (node (ref "R52") (pin "2") (pinfunction "2_2") (pintype "passive"))
      (node (ref "U2") (pin "2") (pinfunction "-IN_2") (pintype "input"))
      (node (ref "VR2") (pin "3") (pinfunction "3_3") (pintype "passive"))
    )
    (net (code "55") (name "Net-(U2A-OUT)") (class "Default")
      (node (ref "C30") (pin "1") (pinfunction "1_1") (pintype "passive"))
      (node (ref "C32") (pin "+") (pinfunction "+_+") (pintype "passive"))
      (node (ref "R47") (pin "2") (pinfunction "2_2") (pintype "passive"))
      (node (ref "U2") (pin "1") (pinfunction "OUT_1") (pintype "output"))
    )
    (net (code "56") (name "Net-(U2B-+IN)") (class "Default")
      (node (ref "R25") (pin "2") (pinfunction "2_2") (pintype "passive"))
      (node (ref "R26") (pin "2") (pinfunction "2_2") (pintype "passive"))
      (node (ref "U2") (pin "5") (pinfunction "+IN_5") (pintype "input"))
    )
    (net (code "57") (name "Net-(U2B--IN)") (class "Default")
      (node (ref "C18") (pin "2") (pinfunction "2_2") (pintype "passive"))
      (node (ref "R27") (pin "1") (pinfunction "1_1") (pintype "passive"))
      (node (ref "R91") (pin "2") (pinfunction "2_2") (pintype "passive"))
      (node (ref "U2") (pin "6") (pinfunction "-IN_6") (pintype "input"))
    )
    (net (code "58") (name "Net-(U2B-OUT)") (class "Default")
      (node (ref "C18") (pin "1") (pinfunction "1_1") (pintype "passive"))
      (node (ref "R29") (pin "1") (pinfunction "1_1") (pintype "passive"))
      (node (ref "U2") (pin "7") (pinfunction "OUT_7") (pintype "output"))
      (node (ref "VR1") (pin "2") (pinfunction "2_2") (pintype "passive"))
      (node (ref "VR1") (pin "3") (pinfunction "3_3") (pintype "passive"))
    )
    (net (code "59") (name "OUT") (class "Default")
      (node (ref "C36") (pin "-") (pinfunction "-_-") (pintype "passive"))
      (node (ref "R58") (pin "2") (pinfunction "2_2") (pintype "passive"))
    )
    (net (code "60") (name "VB") (class "Default")
      (node (ref "C38") (pin "+") (pinfunction "+_+") (pintype "passive"))
      (node (ref "R26") (pin "1") (pinfunction "1_1") (pintype "passive"))
      (node (ref "R31") (pin "1") (pinfunction "1_1") (pintype "passive"))
      (node (ref "R36") (pin "1") (pinfunction "1_1") (pintype "passive"))
      (node (ref "R39") (pin "1") (pinfunction "1_1") (pintype "passive"))
      (node (ref "R42") (pin "1") (pinfunction "1_1") (pintype "passive"))
      (node (ref "R45") (pin "1") (pinfunction "1_1") (pintype "passive"))
      (node (ref "R53") (pin "1") (pinfunction "1_1") (pintype "passive"))
      (node (ref "R59") (pin "2") (pinfunction "2_2") (pintype "passive"))
      (node (ref "R6") (pin "1") (pinfunction "1_1") (pintype "passive"))
      (node (ref "R60") (pin "2") (pinfunction "2_2") (pintype "passive"))
      (node (ref "R65") (pin "1") (pinfunction "1_1") (pintype "passive"))
      (node (ref "R75") (pin "1") (pinfunction "1_1") (pintype "passive"))
      (node (ref "R81") (pin "1") (pinfunction "1_1") (pintype "passive"))
      (node (ref "VR4") (pin "3") (pinfunction "3_3") (pintype "passive"))
    )
  )
)
